# SMPS_5V_Analog.net
KiCad netlist of a schematic drawn in Altium Designer
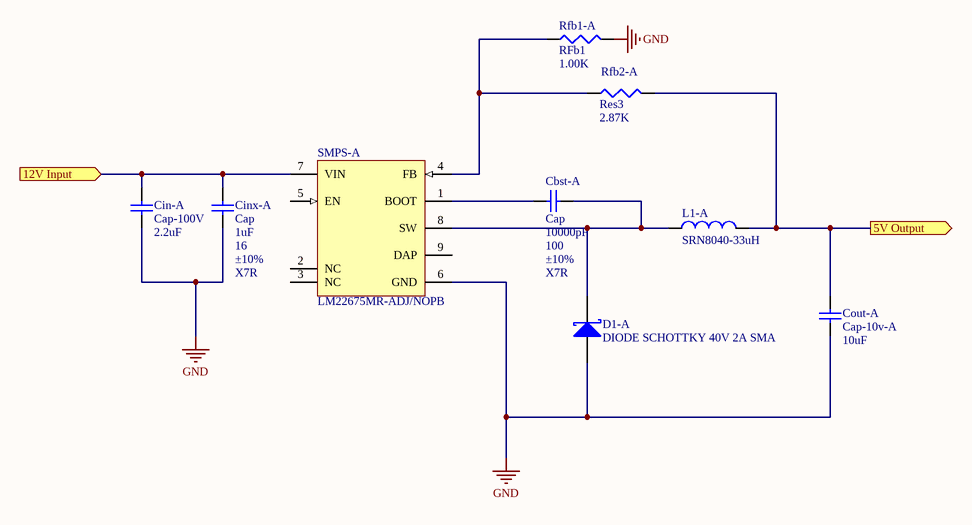
[diagram p0: SMPS_5V_Analog.SchDoc]

(export (version "E")
  (design (tool "Eeschema 10.0.6"))
  (components
    (comp (ref "Cbst-A")
      (value "Cap")
      (footprint "CAPC2012X09M")
      (description "CAP CER 10000pF 100v X7R 0805")
      (fields
        (field (name "ALTIUM_VALUE") "10000pF")
        (field (name "WV") "100")
        (field (name "TOLERANCE") "±10%")
        (field (name "TYPE") "X7R")
        (field (name "MPN") "C0805C103K1RACTU")
      )
      (libsource (lib "esd_library") (part "CAP-X7R-10000pF-100V-±10%"))
    )
    (comp (ref "Cin-A")
      (value "Cap-100V")
      (footprint "Miscellaneous Devices:C1210")
      (description "Capacitor")
      (fields (field (name "ALTIUM_VALUE") "2.2uF") (field (name "PUBLISHER") "Altium Limited"))
      (libsource (lib "Miscellaneous Devices") (part "Cap"))
    )
    (comp (ref "Cinx-A")
      (value "Cap")
      (footprint "CAPC2012X09M")
      (description "CAP CER 1uF 16v X7R 0805")
      (fields
        (field (name "ALTIUM_VALUE") "1uF")
        (field (name "WV") "16")
        (field (name "TOLERANCE") "±10%")
        (field (name "TYPE") "X7R")
        (field (name "MPN") "C0805C105K4RACTU")
      )
      (libsource (lib "esd_library") (part "CAP-X7R-1uF-16V-±10%"))
    )
    (comp (ref "Cout-A")
      (value "Cap-10v-A")
      (footprint "Miscellaneous Devices:C1210")
      (description "Capacitor")
      (fields (field (name "ALTIUM_VALUE") "10uF") (field (name "PUBLISHER") "Altium Limited"))
      (libsource (lib "Miscellaneous Devices") (part "Cap"))
    )
    (comp (ref "D1-A")
      (value "DIODE SCHOTTKY 40V 2A SMA")
      (footprint "DIOM4326X23M")
      (description "Schottky Rectifier")
      (fields (field (name "MPN") "B240A-13-F"))
      (libsource (lib "esd_library") (part "DIODE SCHOTTKY 40V 2A SMA"))
    )
    (comp (ref "L1-A")
      (value "SRN8040-33uH")
      (footprint "INDP8080X40M")
      (description "FIXED IND 22UH 2.2A 100 MOHM SMD")
      (fields (field (name "MPN") "SRN8040-220M"))
      (libsource (lib "esd_library") (part "SRN8040"))
    )
    (comp (ref "Rfb1-A")
      (value "RFb1")
      (footprint "RESC2112X05M")
      (description "RES SMD 1.00K OHM 1% 1/8W 0805")
      (fields (field (name "MPN") "CRCW08051K00FKEA") (field (name "ALTIUM_VALUE") "1.00K"))
      (libsource (lib "esd_library") (part "Resistor_1.00K"))
    )
    (comp (ref "Rfb2-A")
      (value "Res3")
      (footprint "RESC2112X05M")
      (description "RES SMD 2.87K OHM 1% 1/8W 0805")
      (fields (field (name "ALTIUM_VALUE") "2.87K") (field (name "MPN") "CRCW08052K87FKEA"))
      (libsource (lib "esd_library") (part "Resistor_2.87K"))
    )
    (comp (ref "SMPS-A")
      (value "LM22675MR-ADJ/NOPB")
      (footprint "MRA08B_L")
      (description "1A SIMPLE SWITCHER®, Step-Down Voltage Regulator with Precision Enable, 8-pin PSOP, Pb-Free")
      (fields
        (field (name "MANUFACTURER") "National Semiconductor")
        (field (name "MPN") "LM22675MRE-ADJ/NOPB")
      )
      (libsource (lib "esd_library") (part "LM22675MR-ADJ/NOPB"))
    )
  )
  (nets
    (net (code "1") (name "/5V Output") (class "Default")
      (node (ref "Cout-A") (pin "2") (pinfunction "2_2") (pintype "passive"))
      (node (ref "L1-A") (pin "2") (pinfunction "2_2") (pintype "passive"))
      (node (ref "Rfb2-A") (pin "2") (pinfunction "2_2") (pintype "passive"))
    )
    (net (code "2") (name "/12V Input") (class "Default")
      (node (ref "Cin-A") (pin "2") (pinfunction "2_2") (pintype "passive"))
      (node (ref "Cinx-A") (pin "2") (pinfunction "2_2") (pintype "passive"))
      (node (ref "SMPS-A") (pin "7") (pinfunction "VIN_7") (pintype "power_in"))
    )
    (net (code "3") (name "GND") (class "Default")
      (node (ref "Cin-A") (pin "1") (pinfunction "1_1") (pintype "passive"))
      (node (ref "Cinx-A") (pin "1") (pinfunction "1_1") (pintype "passive"))
      (node (ref "Cout-A") (pin "1") (pinfunction "1_1") (pintype "passive"))
      (node (ref "D1-A") (pin "2") (pinfunction "A_2") (pintype "passive"))
      (node (ref "Rfb1-A") (pin "2") (pinfunction "2_2") (pintype "passive"))
      (node (ref "SMPS-A") (pin "6") (pinfunction "GND_6") (pintype "power_in"))
    )
    (net (code "4") (name "Net-(D1-A-K)") (class "Default")
      (node (ref "Cbst-A") (pin "1") (pinfunction "1_1") (pintype "passive"))
      (node (ref "D1-A") (pin "1") (pinfunction "K_1") (pintype "passive"))
      (node (ref "L1-A") (pin "1") (pinfunction "1_1") (pintype "passive"))
      (node (ref "SMPS-A") (pin "8") (pinfunction "SW_8") (pintype "power_in"))
    )
    (net (code "5") (name "Net-(SMPS-A-BOOT)") (class "Default")
      (node (ref "Cbst-A") (pin "2") (pinfunction "2_2") (pintype "passive"))
      (node (ref "SMPS-A") (pin "1") (pinfunction "BOOT_1") (pintype "passive"))
    )
    (net (code "6") (name "Net-(SMPS-A-FB)") (class "Default")
      (node (ref "Rfb1-A") (pin "1") (pinfunction "1_1") (pintype "passive"))
      (node (ref "Rfb2-A") (pin "1") (pinfunction "1_1") (pintype "passive"))
      (node (ref "SMPS-A") (pin "4") (pinfunction "FB_4") (pintype "input"))
    )
    (net (code "7") (name "unconnected-(SMPS-A-DAP-Pad9)") (class "Default")
      (node (ref "SMPS-A") (pin "9") (pinfunction "DAP_9") (pintype "power_in"))
    )
    (net (code "8") (name "unconnected-(SMPS-A-EN-Pad5)") (class "Default")
      (node (ref "SMPS-A") (pin "5") (pinfunction "EN_5") (pintype "input"))
    )
    (net (code "9") (name "unconnected-(SMPS-A-NC-Pad2)") (class "Default")
      (node (ref "SMPS-A") (pin "2") (pinfunction "NC_2") (pintype "passive"))
    )
    (net (code "10") (name "unconnected-(SMPS-A-NC-Pad3)") (class "Default")
      (node (ref "SMPS-A") (pin "3") (pinfunction "NC_3") (pintype "passive"))
    )
  )
)
